# UI_mon.net
KiCad netlist of a schematic drawn in Altium Designer
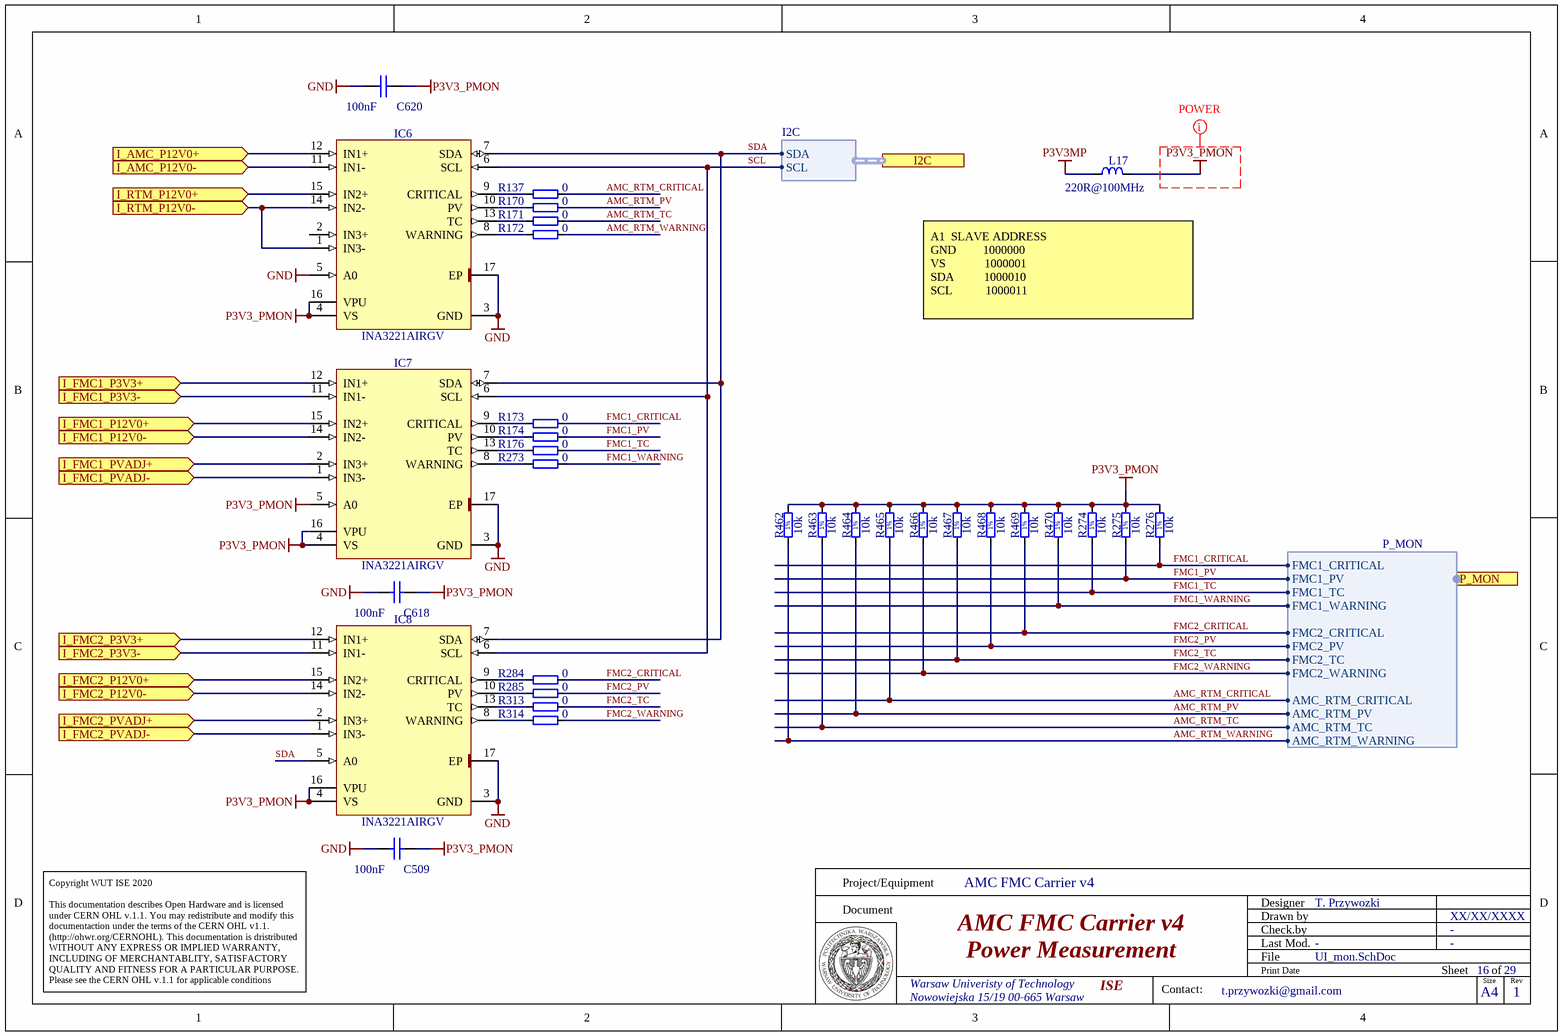
[diagram p0: UI_mon.SchDoc]

(export (version "E")
  (design (tool "Eeschema 10.0.6"))
  (components
    (comp (ref "C509")
      (value "100nF")
      (footprint "CAPC0603X33N")
      (description "Non-polarised capacitor")
      (fields
        (field (name "PART NUMBER") "CC0201_100NF_6.3V_10%_X5R")
        (field (name "VOLTAGE") "6.3V")
        (field (name "AUTHOR") "CERN DEM JLC")
      )
      (libsource (lib "Capacitors") (part "Capacitor - non polarized"))
    )
    (comp (ref "C618")
      (value "100nF")
      (footprint "CAPC0603X33N")
      (description "Non-polarised capacitor")
      (fields
        (field (name "PART NUMBER") "CC0201_100NF_6.3V_10%_X5R")
        (field (name "VOLTAGE") "6.3V")
        (field (name "AUTHOR") "CERN DEM JLC")
      )
      (libsource (lib "Capacitors") (part "Capacitor - non polarized"))
    )
    (comp (ref "C620")
      (value "100nF")
      (footprint "CAPC0603X33N")
      (description "Non-polarised capacitor")
      (fields
        (field (name "PART NUMBER") "CC0201_100NF_6.3V_10%_X5R")
        (field (name "VOLTAGE") "6.3V")
        (field (name "AUTHOR") "CERN DEM JLC")
      )
      (libsource (lib "Capacitors") (part "Capacitor - non polarized"))
    )
    (comp (ref "IC6")
      (value "INA3221AIRGV")
      (footprint "QFN65P400X400X100-17N-S225")
      (fields (field (name "MANUFACTURER") "TEXAS INSTRUMENTS") (field (name "AUTHOR") "CERN DEM MR"))
      (libsource (lib "ICs And Semiconductors") (part "INA3221"))
    )
    (comp (ref "IC7")
      (value "INA3221AIRGV")
      (footprint "QFN65P400X400X100-17N-S225")
      (fields (field (name "MANUFACTURER") "TEXAS INSTRUMENTS") (field (name "AUTHOR") "CERN DEM MR"))
      (libsource (lib "ICs And Semiconductors") (part "INA3221"))
    )
    (comp (ref "IC8")
      (value "INA3221AIRGV")
      (footprint "QFN65P400X400X100-17N-S225")
      (fields (field (name "MANUFACTURER") "TEXAS INSTRUMENTS") (field (name "AUTHOR") "CERN DEM MR"))
      (libsource (lib "ICs And Semiconductors") (part "INA3221"))
    )
    (comp (ref "L17")
      (value "220R@100MHz")
      (footprint "INDC2012X105N")
      (description "Inductor")
      (fields
        (field (name "PART NUMBER") "IND0805_MURATA_BLM21PG221SN1D")
        (field (name "POWER") "2A")
        (field (name "AUTHOR") "CERN DEM JLC")
      )
      (libsource (lib "Inductors & Transformers") (part "Inductor"))
    )
    (comp (ref "R137")
      (value "0")
      (footprint "RESC1005X40N")
      (description "Resistor")
      (fields
        (field (name "PART NUMBER") "R0402_0R_JUMPER")
        (field (name "MANUFACTURER") "GENERIC")
        (field (name "AUTHOR") "CERN DEM JLC")
      )
      (libsource (lib "Resistors") (part "Resistor"))
    )
    (comp (ref "R170")
      (value "0")
      (footprint "RESC1005X40N")
      (description "Resistor")
      (fields
        (field (name "PART NUMBER") "R0402_0R_JUMPER")
        (field (name "MANUFACTURER") "GENERIC")
        (field (name "AUTHOR") "CERN DEM JLC")
      )
      (libsource (lib "Resistors") (part "Resistor"))
    )
    (comp (ref "R171")
      (value "0")
      (footprint "RESC1005X40N")
      (description "Resistor")
      (fields
        (field (name "PART NUMBER") "R0402_0R_JUMPER")
        (field (name "MANUFACTURER") "GENERIC")
        (field (name "AUTHOR") "CERN DEM JLC")
      )
      (libsource (lib "Resistors") (part "Resistor"))
    )
    (comp (ref "R172")
      (value "0")
      (footprint "RESC1005X40N")
      (description "Resistor")
      (fields
        (field (name "PART NUMBER") "R0402_0R_JUMPER")
        (field (name "MANUFACTURER") "GENERIC")
        (field (name "AUTHOR") "CERN DEM JLC")
      )
      (libsource (lib "Resistors") (part "Resistor"))
    )
    (comp (ref "R173")
      (value "0")
      (footprint "RESC1005X40N")
      (description "Resistor")
      (fields
        (field (name "PART NUMBER") "R0402_0R_JUMPER")
        (field (name "MANUFACTURER") "GENERIC")
        (field (name "AUTHOR") "CERN DEM JLC")
      )
      (libsource (lib "Resistors") (part "Resistor"))
    )
    (comp (ref "R174")
      (value "0")
      (footprint "RESC1005X40N")
      (description "Resistor")
      (fields
        (field (name "PART NUMBER") "R0402_0R_JUMPER")
        (field (name "MANUFACTURER") "GENERIC")
        (field (name "AUTHOR") "CERN DEM JLC")
      )
      (libsource (lib "Resistors") (part "Resistor"))
    )
    (comp (ref "R176")
      (value "0")
      (footprint "RESC1005X40N")
      (description "Resistor")
      (fields
        (field (name "PART NUMBER") "R0402_0R_JUMPER")
        (field (name "MANUFACTURER") "GENERIC")
        (field (name "AUTHOR") "CERN DEM JLC")
      )
      (libsource (lib "Resistors") (part "Resistor"))
    )
    (comp (ref "R273")
      (value "0")
      (footprint "RESC1005X40N")
      (description "Resistor")
      (fields
        (field (name "PART NUMBER") "R0402_0R_JUMPER")
        (field (name "MANUFACTURER") "GENERIC")
        (field (name "AUTHOR") "CERN DEM JLC")
      )
      (libsource (lib "Resistors") (part "Resistor"))
    )
    (comp (ref "R274")
      (value "10k")
      (footprint "RESC1005X40N")
      (description "Resistor - 1%")
      (fields
        (field (name "MANUFACTURER PART NUMBER") "R0402_10K_1%_0.0625W_100PPM")
        (field (name "MANUFACTURER") "GENERIC")
        (field (name "AUTHOR") "CERN DEM JLC")
      )
      (libsource (lib "Resistors") (part "Resistor - 1%"))
    )
    (comp (ref "R275")
      (value "10k")
      (footprint "RESC1005X40N")
      (description "Resistor - 1%")
      (fields
        (field (name "MANUFACTURER PART NUMBER") "R0402_10K_1%_0.0625W_100PPM")
        (field (name "MANUFACTURER") "GENERIC")
        (field (name "AUTHOR") "CERN DEM JLC")
      )
      (libsource (lib "Resistors") (part "Resistor - 1%"))
    )
    (comp (ref "R276")
      (value "10k")
      (footprint "RESC1005X40N")
      (description "Resistor - 1%")
      (fields
        (field (name "MANUFACTURER PART NUMBER") "R0402_10K_1%_0.0625W_100PPM")
        (field (name "MANUFACTURER") "GENERIC")
        (field (name "AUTHOR") "CERN DEM JLC")
      )
      (libsource (lib "Resistors") (part "Resistor - 1%"))
    )
    (comp (ref "R284")
      (value "0")
      (footprint "RESC1005X40N")
      (description "Resistor")
      (fields
        (field (name "PART NUMBER") "R0402_0R_JUMPER")
        (field (name "MANUFACTURER") "GENERIC")
        (field (name "AUTHOR") "CERN DEM JLC")
      )
      (libsource (lib "Resistors") (part "Resistor"))
    )
    (comp (ref "R285")
      (value "0")
      (footprint "RESC1005X40N")
      (description "Resistor")
      (fields
        (field (name "PART NUMBER") "R0402_0R_JUMPER")
        (field (name "MANUFACTURER") "GENERIC")
        (field (name "AUTHOR") "CERN DEM JLC")
      )
      (libsource (lib "Resistors") (part "Resistor"))
    )
    (comp (ref "R313")
      (value "0")
      (footprint "RESC1005X40N")
      (description "Resistor")
      (fields
        (field (name "PART NUMBER") "R0402_0R_JUMPER")
        (field (name "MANUFACTURER") "GENERIC")
        (field (name "AUTHOR") "CERN DEM JLC")
      )
      (libsource (lib "Resistors") (part "Resistor"))
    )
    (comp (ref "R314")
      (value "0")
      (footprint "RESC1005X40N")
      (description "Resistor")
      (fields
        (field (name "PART NUMBER") "R0402_0R_JUMPER")
        (field (name "MANUFACTURER") "GENERIC")
        (field (name "AUTHOR") "CERN DEM JLC")
      )
      (libsource (lib "Resistors") (part "Resistor"))
    )
    (comp (ref "R462")
      (value "10k")
      (footprint "RESC1005X40N")
      (description "Resistor - 1%")
      (fields
        (field (name "MANUFACTURER PART NUMBER") "R0402_10K_1%_0.0625W_100PPM")
        (field (name "MANUFACTURER") "GENERIC")
        (field (name "AUTHOR") "CERN DEM JLC")
      )
      (libsource (lib "Resistors") (part "Resistor - 1%"))
    )
    (comp (ref "R463")
      (value "10k")
      (footprint "RESC1005X40N")
      (description "Resistor - 1%")
      (fields
        (field (name "MANUFACTURER PART NUMBER") "R0402_10K_1%_0.0625W_100PPM")
        (field (name "MANUFACTURER") "GENERIC")
        (field (name "AUTHOR") "CERN DEM JLC")
      )
      (libsource (lib "Resistors") (part "Resistor - 1%"))
    )
    (comp (ref "R464")
      (value "10k")
      (footprint "RESC1005X40N")
      (description "Resistor - 1%")
      (fields
        (field (name "MANUFACTURER PART NUMBER") "R0402_10K_1%_0.0625W_100PPM")
        (field (name "MANUFACTURER") "GENERIC")
        (field (name "AUTHOR") "CERN DEM JLC")
      )
      (libsource (lib "Resistors") (part "Resistor - 1%"))
    )
    (comp (ref "R465")
      (value "10k")
      (footprint "RESC1005X40N")
      (description "Resistor - 1%")
      (fields
        (field (name "MANUFACTURER PART NUMBER") "R0402_10K_1%_0.0625W_100PPM")
        (field (name "MANUFACTURER") "GENERIC")
        (field (name "AUTHOR") "CERN DEM JLC")
      )
      (libsource (lib "Resistors") (part "Resistor - 1%"))
    )
    (comp (ref "R466")
      (value "10k")
      (footprint "RESC1005X40N")
      (description "Resistor - 1%")
      (fields
        (field (name "MANUFACTURER PART NUMBER") "R0402_10K_1%_0.0625W_100PPM")
        (field (name "MANUFACTURER") "GENERIC")
        (field (name "AUTHOR") "CERN DEM JLC")
      )
      (libsource (lib "Resistors") (part "Resistor - 1%"))
    )
    (comp (ref "R467")
      (value "10k")
      (footprint "RESC1005X40N")
      (description "Resistor - 1%")
      (fields
        (field (name "MANUFACTURER PART NUMBER") "R0402_10K_1%_0.0625W_100PPM")
        (field (name "MANUFACTURER") "GENERIC")
        (field (name "AUTHOR") "CERN DEM JLC")
      )
      (libsource (lib "Resistors") (part "Resistor - 1%"))
    )
    (comp (ref "R468")
      (value "10k")
      (footprint "RESC1005X40N")
      (description "Resistor - 1%")
      (fields
        (field (name "MANUFACTURER PART NUMBER") "R0402_10K_1%_0.0625W_100PPM")
        (field (name "MANUFACTURER") "GENERIC")
        (field (name "AUTHOR") "CERN DEM JLC")
      )
      (libsource (lib "Resistors") (part "Resistor - 1%"))
    )
    (comp (ref "R469")
      (value "10k")
      (footprint "RESC1005X40N")
      (description "Resistor - 1%")
      (fields
        (field (name "MANUFACTURER PART NUMBER") "R0402_10K_1%_0.0625W_100PPM")
        (field (name "MANUFACTURER") "GENERIC")
        (field (name "AUTHOR") "CERN DEM JLC")
      )
      (libsource (lib "Resistors") (part "Resistor - 1%"))
    )
    (comp (ref "R470")
      (value "10k")
      (footprint "RESC1005X40N")
      (description "Resistor - 1%")
      (fields
        (field (name "MANUFACTURER PART NUMBER") "R0402_10K_1%_0.0625W_100PPM")
        (field (name "MANUFACTURER") "GENERIC")
        (field (name "AUTHOR") "CERN DEM JLC")
      )
      (libsource (lib "Resistors") (part "Resistor - 1%"))
    )
  )
  (nets
    (net (code "3") (name "/AMC_RTM_CRITICAL") (class "Default")
      (node (ref "R137") (pin "2") (pinfunction "2_2") (pintype "passive"))
      (node (ref "R465") (pin "1") (pinfunction "1_1") (pintype "passive"))
    )
    (net (code "4") (name "/AMC_RTM_PV") (class "Default")
      (node (ref "R170") (pin "2") (pinfunction "2_2") (pintype "passive"))
      (node (ref "R464") (pin "1") (pinfunction "1_1") (pintype "passive"))
    )
    (net (code "5") (name "/AMC_RTM_TC") (class "Default")
      (node (ref "R171") (pin "2") (pinfunction "2_2") (pintype "passive"))
      (node (ref "R463") (pin "1") (pinfunction "1_1") (pintype "passive"))
    )
    (net (code "6") (name "/AMC_RTM_WARNING") (class "Default")
      (node (ref "R172") (pin "2") (pinfunction "2_2") (pintype "passive"))
      (node (ref "R462") (pin "1") (pinfunction "1_1") (pintype "passive"))
    )
    (net (code "7") (name "/FMC1_CRITICAL") (class "Default")
      (node (ref "R173") (pin "2") (pinfunction "2_2") (pintype "passive"))
      (node (ref "R276") (pin "1") (pinfunction "1_1") (pintype "passive"))
    )
    (net (code "8") (name "/FMC1_PV") (class "Default")
      (node (ref "R174") (pin "2") (pinfunction "2_2") (pintype "passive"))
      (node (ref "R275") (pin "1") (pinfunction "1_1") (pintype "passive"))
    )
    (net (code "9") (name "/FMC1_TC") (class "Default")
      (node (ref "R176") (pin "2") (pinfunction "2_2") (pintype "passive"))
      (node (ref "R274") (pin "1") (pinfunction "1_1") (pintype "passive"))
    )
    (net (code "10") (name "/FMC1_WARNING") (class "Default")
      (node (ref "R273") (pin "2") (pinfunction "2_2") (pintype "passive"))
      (node (ref "R470") (pin "1") (pinfunction "1_1") (pintype "passive"))
    )
    (net (code "11") (name "/FMC2_CRITICAL") (class "Default")
      (node (ref "R284") (pin "2") (pinfunction "2_2") (pintype "passive"))
      (node (ref "R469") (pin "1") (pinfunction "1_1") (pintype "passive"))
    )
    (net (code "12") (name "/FMC2_PV") (class "Default")
      (node (ref "R285") (pin "2") (pinfunction "2_2") (pintype "passive"))
      (node (ref "R468") (pin "1") (pinfunction "1_1") (pintype "passive"))
    )
    (net (code "13") (name "/FMC2_TC") (class "Default")
      (node (ref "R313") (pin "2") (pinfunction "2_2") (pintype "passive"))
      (node (ref "R467") (pin "1") (pinfunction "1_1") (pintype "passive"))
    )
    (net (code "14") (name "/FMC2_WARNING") (class "Default")
      (node (ref "R314") (pin "2") (pinfunction "2_2") (pintype "passive"))
      (node (ref "R466") (pin "1") (pinfunction "1_1") (pintype "passive"))
    )
    (net (code "15") (name "/I_AMC_P12V0+") (class "Default")
      (node (ref "IC6") (pin "12") (pinfunction "IN1+_12") (pintype "input"))
    )
    (net (code "16") (name "/I_AMC_P12V0-") (class "Default")
      (node (ref "IC6") (pin "11") (pinfunction "IN1-_11") (pintype "input"))
    )
    (net (code "17") (name "/I_FMC1_P3V3+") (class "Default")
      (node (ref "IC7") (pin "12") (pinfunction "IN1+_12") (pintype "input"))
    )
    (net (code "18") (name "/I_FMC1_P3V3-") (class "Default")
      (node (ref "IC7") (pin "11") (pinfunction "IN1-_11") (pintype "input"))
    )
    (net (code "19") (name "/I_FMC1_P12V0+") (class "Default")
      (node (ref "IC7") (pin "15") (pinfunction "IN2+_15") (pintype "input"))
    )
    (net (code "20") (name "/I_FMC1_P12V0-") (class "Default")
      (node (ref "IC7") (pin "14") (pinfunction "IN2-_14") (pintype "input"))
    )
    (net (code "21") (name "/I_FMC1_PVADJ+") (class "Default")
      (node (ref "IC7") (pin "2") (pinfunction "IN3+_2") (pintype "input"))
    )
    (net (code "22") (name "/I_FMC1_PVADJ-") (class "Default")
      (node (ref "IC7") (pin "1") (pinfunction "IN3-_1") (pintype "input"))
    )
    (net (code "23") (name "/I_FMC2_P3V3+") (class "Default")
      (node (ref "IC8") (pin "12") (pinfunction "IN1+_12") (pintype "input"))
    )
    (net (code "24") (name "/I_FMC2_P3V3-") (class "Default")
      (node (ref "IC8") (pin "11") (pinfunction "IN1-_11") (pintype "input"))
    )
    (net (code "25") (name "/I_FMC2_P12V0+") (class "Default")
      (node (ref "IC8") (pin "15") (pinfunction "IN2+_15") (pintype "input"))
    )
    (net (code "26") (name "/I_FMC2_P12V0-") (class "Default")
      (node (ref "IC8") (pin "14") (pinfunction "IN2-_14") (pintype "input"))
    )
    (net (code "27") (name "/I_FMC2_PVADJ+") (class "Default")
      (node (ref "IC8") (pin "2") (pinfunction "IN3+_2") (pintype "input"))
    )
    (net (code "28") (name "/I_FMC2_PVADJ-") (class "Default")
      (node (ref "IC8") (pin "1") (pinfunction "IN3-_1") (pintype "input"))
    )
    (net (code "29") (name "/I_RTM_P12V0+") (class "Default")
      (node (ref "IC6") (pin "15") (pinfunction "IN2+_15") (pintype "input"))
    )
    (net (code "30") (name "/I_RTM_P12V0-") (class "Default")
      (node (ref "IC6") (pin "1") (pinfunction "IN3-_1") (pintype "input"))
      (node (ref "IC6") (pin "14") (pinfunction "IN2-_14") (pintype "input"))
    )
    (net (code "31") (name "/SCL") (class "Default")
      (node (ref "IC6") (pin "6") (pinfunction "SCL_6") (pintype "input"))
      (node (ref "IC7") (pin "6") (pinfunction "SCL_6") (pintype "input"))
      (node (ref "IC8") (pin "6") (pinfunction "SCL_6") (pintype "input"))
    )
    (net (code "32") (name "/SDA") (class "Default")
      (node (ref "IC6") (pin "7") (pinfunction "SDA_7") (pintype "bidirectional"))
      (node (ref "IC7") (pin "7") (pinfunction "SDA_7") (pintype "bidirectional"))
      (node (ref "IC8") (pin "5") (pinfunction "A0_5") (pintype "input"))
      (node (ref "IC8") (pin "7") (pinfunction "SDA_7") (pintype "bidirectional"))
    )
    (net (code "35") (name "GND") (class "Default")
      (node (ref "C509") (pin "2") (pinfunction "2_2") (pintype "passive"))
      (node (ref "C618") (pin "2") (pinfunction "2_2") (pintype "passive"))
      (node (ref "C620") (pin "2") (pinfunction "2_2") (pintype "passive"))
      (node (ref "IC6") (pin "17") (pinfunction "EP_17") (pintype "power_in"))
      (node (ref "IC6") (pin "3") (pinfunction "GND_3") (pintype "power_in"))
      (node (ref "IC6") (pin "5") (pinfunction "A0_5") (pintype "input"))
      (node (ref "IC7") (pin "17") (pinfunction "EP_17") (pintype "power_in"))
      (node (ref "IC7") (pin "3") (pinfunction "GND_3") (pintype "power_in"))
      (node (ref "IC8") (pin "17") (pinfunction "EP_17") (pintype "power_in"))
      (node (ref "IC8") (pin "3") (pinfunction "GND_3") (pintype "power_in"))
    )
    (net (code "36") (name "Net-(IC6-CRITICAL)") (class "Default")
      (node (ref "IC6") (pin "9") (pinfunction "CRITICAL_9") (pintype "output"))
      (node (ref "R137") (pin "1") (pinfunction "1_1") (pintype "passive"))
    )
    (net (code "37") (name "Net-(IC6-PV)") (class "Default")
      (node (ref "IC6") (pin "10") (pinfunction "PV_10") (pintype "output"))
      (node (ref "R170") (pin "1") (pinfunction "1_1") (pintype "passive"))
    )
    (net (code "38") (name "Net-(IC6-TC)") (class "Default")
      (node (ref "IC6") (pin "13") (pinfunction "TC_13") (pintype "output"))
      (node (ref "R171") (pin "1") (pinfunction "1_1") (pintype "passive"))
    )
    (net (code "39") (name "Net-(IC6-WARNING)") (class "Default")
      (node (ref "IC6") (pin "8") (pinfunction "WARNING_8") (pintype "output"))
      (node (ref "R172") (pin "1") (pinfunction "1_1") (pintype "passive"))
    )
    (net (code "40") (name "Net-(IC7-CRITICAL)") (class "Default")
      (node (ref "IC7") (pin "9") (pinfunction "CRITICAL_9") (pintype "output"))
      (node (ref "R173") (pin "1") (pinfunction "1_1") (pintype "passive"))
    )
    (net (code "41") (name "Net-(IC7-PV)") (class "Default")
      (node (ref "IC7") (pin "10") (pinfunction "PV_10") (pintype "output"))
      (node (ref "R174") (pin "1") (pinfunction "1_1") (pintype "passive"))
    )
    (net (code "42") (name "Net-(IC7-TC)") (class "Default")
      (node (ref "IC7") (pin "13") (pinfunction "TC_13") (pintype "output"))
      (node (ref "R176") (pin "1") (pinfunction "1_1") (pintype "passive"))
    )
    (net (code "43") (name "Net-(IC7-WARNING)") (class "Default")
      (node (ref "IC7") (pin "8") (pinfunction "WARNING_8") (pintype "output"))
      (node (ref "R273") (pin "1") (pinfunction "1_1") (pintype "passive"))
    )
    (net (code "44") (name "Net-(IC8-CRITICAL)") (class "Default")
      (node (ref "IC8") (pin "9") (pinfunction "CRITICAL_9") (pintype "output"))
      (node (ref "R284") (pin "1") (pinfunction "1_1") (pintype "passive"))
    )
    (net (code "45") (name "Net-(IC8-PV)") (class "Default")
      (node (ref "IC8") (pin "10") (pinfunction "PV_10") (pintype "output"))
      (node (ref "R285") (pin "1") (pinfunction "1_1") (pintype "passive"))
    )
    (net (code "46") (name "Net-(IC8-TC)") (class "Default")
      (node (ref "IC8") (pin "13") (pinfunction "TC_13") (pintype "output"))
      (node (ref "R313") (pin "1") (pinfunction "1_1") (pintype "passive"))
    )
    (net (code "47") (name "Net-(IC8-WARNING)") (class "Default")
      (node (ref "IC8") (pin "8") (pinfunction "WARNING_8") (pintype "output"))
      (node (ref "R314") (pin "1") (pinfunction "1_1") (pintype "passive"))
    )
    (net (code "48") (name "P3V3MP") (class "Default")
      (node (ref "L17") (pin "1") (pinfunction "1_1") (pintype "passive"))
    )
    (net (code "49") (name "P3V3_PMON") (class "Default")
      (node (ref "C509") (pin "1") (pinfunction "1_1") (pintype "passive"))
      (node (ref "C618") (pin "1") (pinfunction "1_1") (pintype "passive"))
      (node (ref "C620") (pin "1") (pinfunction "1_1") (pintype "passive"))
      (node (ref "IC6") (pin "16") (pinfunction "VPU_16") (pintype "power_in"))
      (node (ref "IC6") (pin "4") (pinfunction "VS_4") (pintype "power_in"))
      (node (ref "IC7") (pin "16") (pinfunction "VPU_16") (pintype "power_in"))
      (node (ref "IC7") (pin "4") (pinfunction "VS_4") (pintype "power_in"))
      (node (ref "IC7") (pin "5") (pinfunction "A0_5") (pintype "input"))
      (node (ref "IC8") (pin "16") (pinfunction "VPU_16") (pintype "power_in"))
      (node (ref "IC8") (pin "4") (pinfunction "VS_4") (pintype "power_in"))
      (node (ref "L17") (pin "2") (pinfunction "2_2") (pintype "passive"))
      (node (ref "R274") (pin "2") (pinfunction "2_2") (pintype "passive"))
      (node (ref "R275") (pin "2") (pinfunction "2_2") (pintype "passive"))
      (node (ref "R276") (pin "2") (pinfunction "2_2") (pintype "passive"))
      (node (ref "R462") (pin "2") (pinfunction "2_2") (pintype "passive"))
      (node (ref "R463") (pin "2") (pinfunction "2_2") (pintype "passive"))
      (node (ref "R464") (pin "2") (pinfunction "2_2") (pintype "passive"))
      (node (ref "R465") (pin "2") (pinfunction "2_2") (pintype "passive"))
      (node (ref "R466") (pin "2") (pinfunction "2_2") (pintype "passive"))
      (node (ref "R467") (pin "2") (pinfunction "2_2") (pintype "passive"))
      (node (ref "R468") (pin "2") (pinfunction "2_2") (pintype "passive"))
      (node (ref "R469") (pin "2") (pinfunction "2_2") (pintype "passive"))
      (node (ref "R470") (pin "2") (pinfunction "2_2") (pintype "passive"))
    )
    (net (code "50") (name "unconnected-(IC6-IN3+-Pad2)") (class "Default")
      (node (ref "IC6") (pin "2") (pinfunction "IN3+_2") (pintype "input"))
    )
  )
)
